# Extruder_Stepper_Motor_Driver.net
KiCad netlist of a schematic drawn in Altium Designer
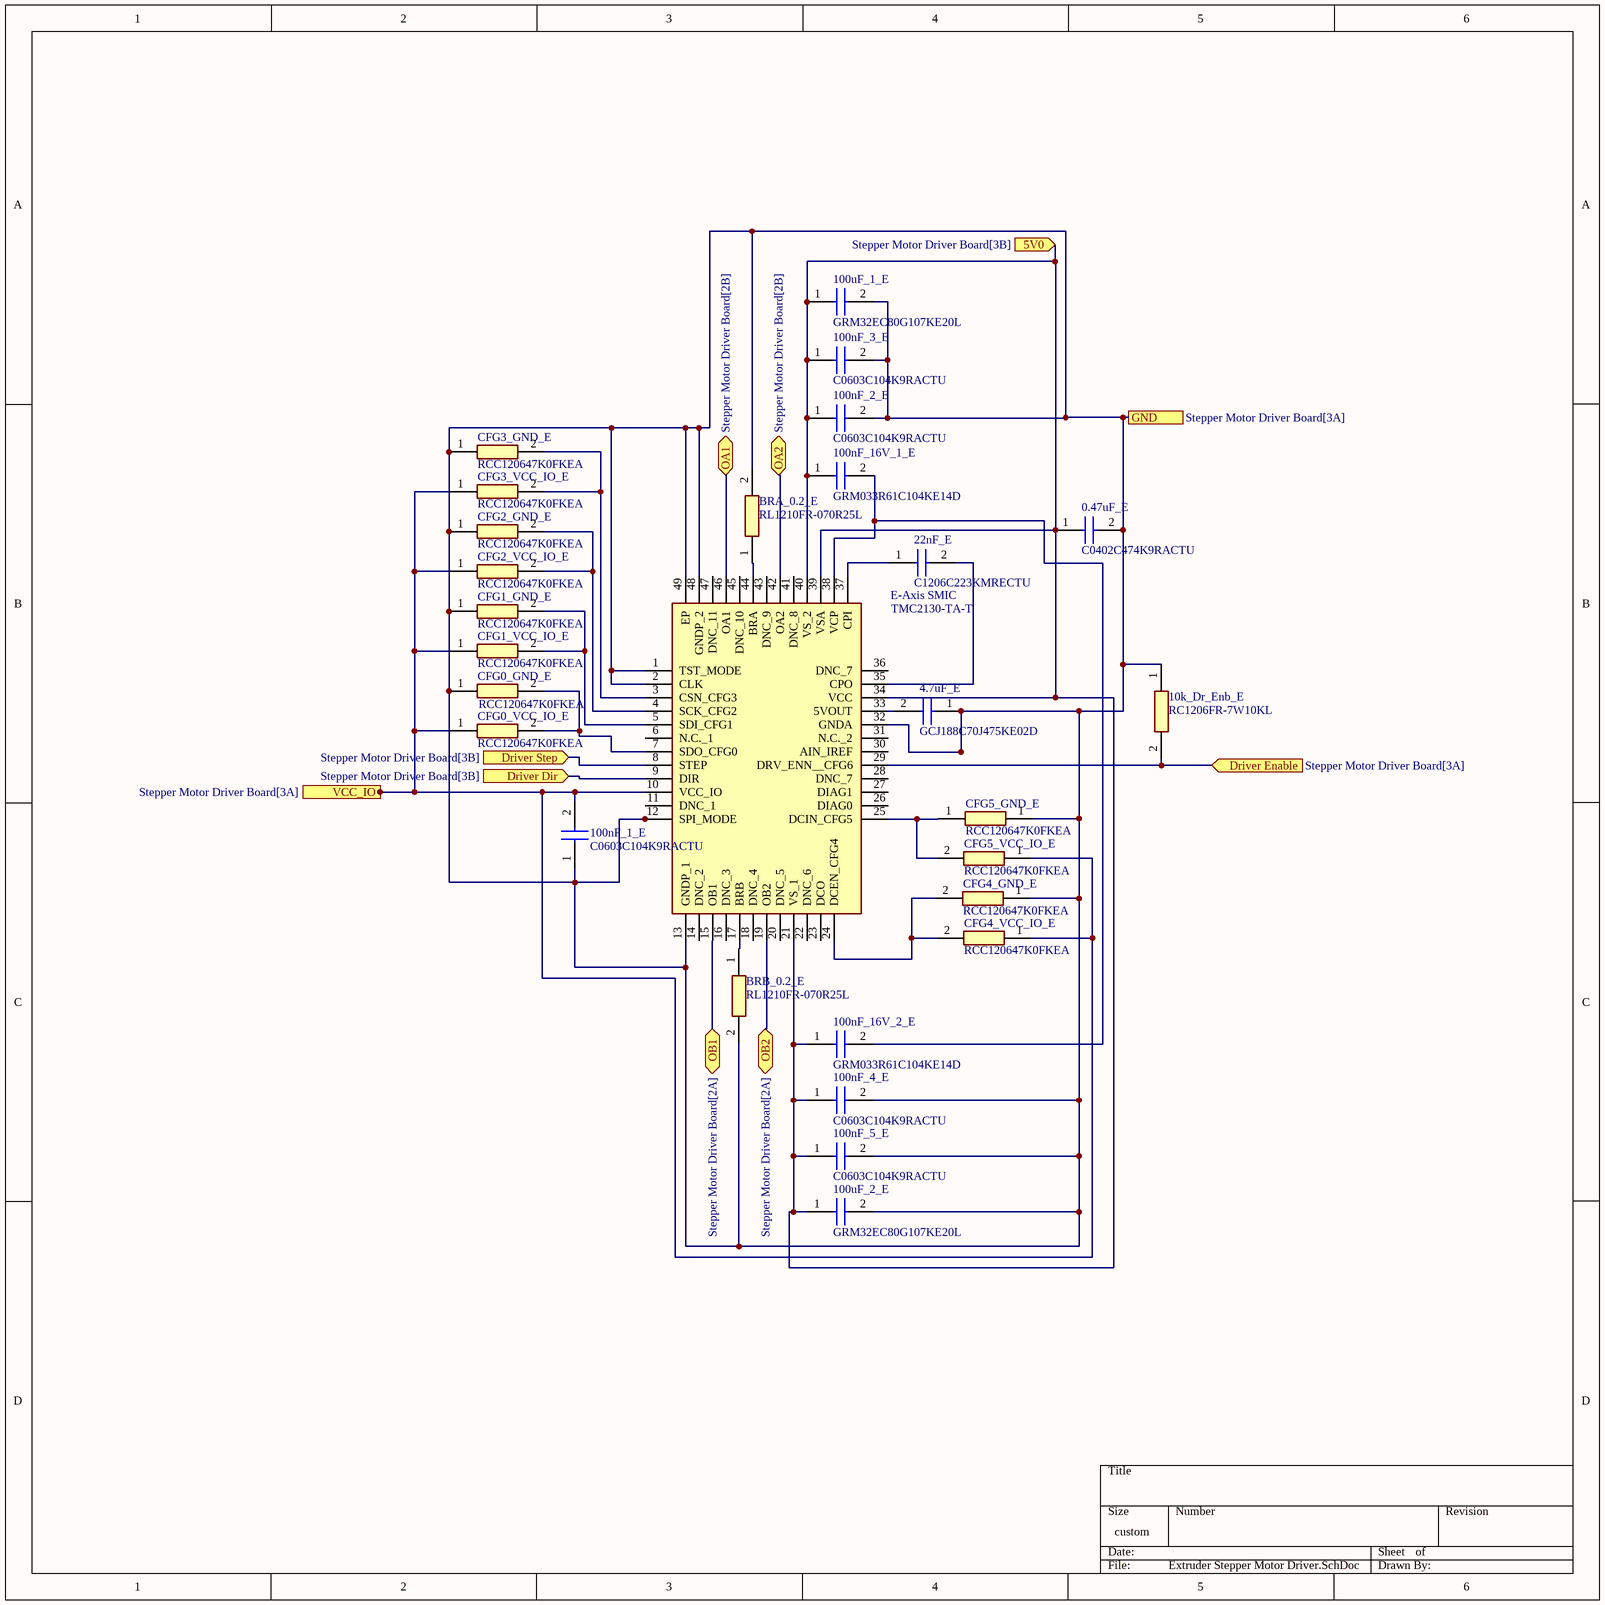
[diagram p0: Extruder Stepper Motor Driver.SchDoc]

(export (version "E")
  (design (tool "Eeschema 10.0.6"))
  (components
    (comp (ref "0.47uF_E")
      (value "C0402C474K9RACTU")
      (footprint "SamacSys:CAPC1005X55N")
      (description "Capacitor")
      (fields (field (name "MOUSER PART NUMBER") "80-C0402C474K9RACTU"))
      (libsource (lib "*") (part "C0402C474K9RACTU"))
    )
    (comp (ref "4.7uF_E")
      (value "GCJ188C70J475KE02D")
      (footprint "SamacSys:CAPC1608X100N")
      (description "Capacitor")
      (fields (field (name "MOUSER PART NUMBER") "81-GCJ188C70J475KE2D"))
      (libsource (lib "*") (part "GCJ188C70J475KE02D"))
    )
    (comp (ref "10k_Dr_Enb_E")
      (value "RC1206FR-7W10KL")
      (footprint "SamacSys:RESC3116X65N")
      (description "Resistor")
      (libsource (lib "*") (part "RC1206FR-7W10KL"))
    )
    (comp (ref "22nF_E")
      (value "C1206C223KMRECTU")
      (footprint "SamacSys:C1206")
      (description "Capacitor")
      (fields (field (name "MOUSER PART NUMBER") "80-C1206C223KMRECTU"))
      (libsource (lib "*") (part "C1206C223KMRECTU"))
    )
    (comp (ref "100nF_1_E")
      (value "C0603C104K9RACTU")
      (footprint "SamacSys:C0603")
      (description "Capacitor")
      (fields (field (name "MOUSER PART NUMBER") "80-C0603C104K9R"))
      (libsource (lib "*") (part "C0603C104K9RACTU"))
    )
    (comp (ref "100nF_2_E")
      (value "C0603C104K9RACTU")
      (footprint "SamacSys:C0603")
      (description "Capacitor")
      (fields (field (name "MOUSER PART NUMBER") "80-C0603C104K9R"))
      (libsource (lib "*") (part "C0603C104K9RACTU"))
    )
    (comp (ref "100nF_3_E")
      (value "C0603C104K9RACTU")
      (footprint "SamacSys:C0603")
      (description "Capacitor")
      (fields (field (name "MOUSER PART NUMBER") "80-C0603C104K9R"))
      (libsource (lib "*") (part "C0603C104K9RACTU"))
    )
    (comp (ref "100nF_4_E")
      (value "C0603C104K9RACTU")
      (footprint "SamacSys:C0603")
      (description "Capacitor")
      (fields (field (name "MOUSER PART NUMBER") "80-C0603C104K9R"))
      (libsource (lib "*") (part "C0603C104K9RACTU"))
    )
    (comp (ref "100nF_5_E")
      (value "C0603C104K9RACTU")
      (footprint "SamacSys:C0603")
      (description "Capacitor")
      (fields (field (name "MOUSER PART NUMBER") "80-C0603C104K9R"))
      (libsource (lib "*") (part "C0603C104K9RACTU"))
    )
    (comp (ref "100nF_16V_1_E")
      (value "GRM033R61C104KE14D")
      (footprint "SamacSys:CAPC0603X33N")
      (description "Capacitor")
      (fields (field (name "MOUSER PART NUMBER") "81-GRM033R61C104KE4D"))
      (libsource (lib "*") (part "GRM033R61C104KE14D"))
    )
    (comp (ref "100nF_16V_2_E")
      (value "GRM033R61C104KE14D")
      (footprint "SamacSys:CAPC0603X33N")
      (description "Capacitor")
      (fields (field (name "MOUSER PART NUMBER") "81-GRM033R61C104KE4D"))
      (libsource (lib "*") (part "GRM033R61C104KE14D"))
    )
    (comp (ref "100uF_1_E")
      (value "GRM32EC80G107KE20L")
      (footprint "SamacSys:CAPC3225X270N")
      (description "Capacitor")
      (fields (field (name "MOUSER PART NUMBER") "81-GRM32EC80G107KE0L"))
      (libsource (lib "*") (part "GRM32EC80G107KE20L"))
    )
    (comp (ref "100uF_2_E")
      (value "GRM32EC80G107KE20L")
      (footprint "SamacSys:CAPC3225X270N")
      (description "Capacitor")
      (fields (field (name "MOUSER PART NUMBER") "81-GRM32EC80G107KE0L"))
      (libsource (lib "*") (part "GRM32EC80G107KE20L"))
    )
    (comp (ref "BRA_0.2_E")
      (value "RL1210FR-070R25L")
      (footprint "SamacSys:RESC3126X65N")
      (description "Resistor")
      (fields (field (name "MOUSER PART NUMBER") "603-RL1210FR-070R25L"))
      (libsource (lib "") (part "RL1210FR-070R25L_1"))
    )
    (comp (ref "BRB_0.2_E")
      (value "RL1210FR-070R25L")
      (footprint "SamacSys:RESC3126X65N")
      (description "Resistor")
      (fields (field (name "MOUSER PART NUMBER") "603-RL1210FR-070R25L"))
      (libsource (lib "*") (part "RL1210FR-070R25L"))
    )
    (comp (ref "CFG0_GND_E")
      (value "RCC120647K0FKEA")
      (footprint "SamacSys:RCC1206_e3")
      (description "Resistor")
      (fields (field (name "MOUSER PART NUMBER") "71-RCC120647K0FKEA"))
      (libsource (lib "") (part "RCC120647K0FKEA_1"))
    )
    (comp (ref "CFG0_VCC_IO_E")
      (value "RCC120647K0FKEA")
      (footprint "SamacSys:RCC1206_e3")
      (description "Resistor")
      (fields (field (name "MOUSER PART NUMBER") "71-RCC120647K0FKEA"))
      (libsource (lib "") (part "RCC120647K0FKEA_1"))
    )
    (comp (ref "CFG1_GND_E")
      (value "RCC120647K0FKEA")
      (footprint "SamacSys:RCC1206_e3")
      (description "Resistor")
      (fields (field (name "MOUSER PART NUMBER") "71-RCC120647K0FKEA"))
      (libsource (lib "") (part "RCC120647K0FKEA_1"))
    )
    (comp (ref "CFG1_VCC_IO_E")
      (value "RCC120647K0FKEA")
      (footprint "SamacSys:RCC1206_e3")
      (description "Resistor")
      (fields (field (name "MOUSER PART NUMBER") "71-RCC120647K0FKEA"))
      (libsource (lib "") (part "RCC120647K0FKEA_1"))
    )
    (comp (ref "CFG2_GND_E")
      (value "RCC120647K0FKEA")
      (footprint "SamacSys:RCC1206_e3")
      (description "Resistor")
      (fields (field (name "MOUSER PART NUMBER") "71-RCC120647K0FKEA"))
      (libsource (lib "") (part "RCC120647K0FKEA_1"))
    )
    (comp (ref "CFG2_VCC_IO_E")
      (value "RCC120647K0FKEA")
      (footprint "SamacSys:RCC1206_e3")
      (description "Resistor")
      (fields (field (name "MOUSER PART NUMBER") "71-RCC120647K0FKEA"))
      (libsource (lib "") (part "RCC120647K0FKEA_1"))
    )
    (comp (ref "CFG3_GND_E")
      (value "RCC120647K0FKEA")
      (footprint "SamacSys:RCC1206_e3")
      (description "Resistor")
      (fields (field (name "MOUSER PART NUMBER") "71-RCC120647K0FKEA"))
      (libsource (lib "") (part "RCC120647K0FKEA_1"))
    )
    (comp (ref "CFG3_VCC_IO_E")
      (value "RCC120647K0FKEA")
      (footprint "SamacSys:RCC1206_e3")
      (description "Resistor")
      (fields (field (name "MOUSER PART NUMBER") "71-RCC120647K0FKEA"))
      (libsource (lib "") (part "RCC120647K0FKEA_1"))
    )
    (comp (ref "CFG4_GND_E")
      (value "RCC120647K0FKEA")
      (footprint "SamacSys:RCC1206_e3")
      (description "Resistor")
      (fields (field (name "MOUSER PART NUMBER") "71-RCC120647K0FKEA"))
      (libsource (lib "*") (part "RCC120647K0FKEA"))
    )
    (comp (ref "CFG4_VCC_IO_E")
      (value "RCC120647K0FKEA")
      (footprint "SamacSys:RCC1206_e3")
      (description "Resistor")
      (fields (field (name "MOUSER PART NUMBER") "71-RCC120647K0FKEA"))
      (libsource (lib "*") (part "RCC120647K0FKEA"))
    )
    (comp (ref "CFG5_GND_E")
      (value "RCC120647K0FKEA")
      (footprint "SamacSys:RCC1206_e3")
      (description "Resistor")
      (fields (field (name "MOUSER PART NUMBER") "71-RCC120647K0FKEA"))
      (libsource (lib "") (part "RCC120647K0FKEA_2"))
    )
    (comp (ref "CFG5_VCC_IO_E")
      (value "RCC120647K0FKEA")
      (footprint "SamacSys:RCC1206_e3")
      (description "Resistor")
      (fields (field (name "MOUSER PART NUMBER") "71-RCC120647K0FKEA"))
      (libsource (lib "*") (part "RCC120647K0FKEA"))
    )
    (comp (ref "E-Axis SMIC")
      (value "TMC2130-TA-T")
      (footprint "SamacSys:QFP50P900X900X120-49N")
      (description "Integrated Circuit")
      (fields (field (name "MOUSER PART NUMBER") "700-TMC2130-TA-T"))
      (libsource (lib "*") (part "TMC2130-TA-T"))
    )
  )
  (nets
    (net (code "1") (name "/5V0") (class "Default")
      (node (ref "0.47uF_E") (pin "1") (pinfunction "1_1") (pintype "passive"))
      (node (ref "100nF_16V_1_E") (pin "1") (pinfunction "1_1") (pintype "passive"))
      (node (ref "100nF_16V_2_E") (pin "1") (pinfunction "1_1") (pintype "passive"))
      (node (ref "100nF_2_E") (pin "1") (pinfunction "1_1") (pintype "passive"))
      (node (ref "100nF_3_E") (pin "1") (pinfunction "1_1") (pintype "passive"))
      (node (ref "100nF_4_E") (pin "1") (pinfunction "1_1") (pintype "passive"))
      (node (ref "100nF_5_E") (pin "1") (pinfunction "1_1") (pintype "passive"))
      (node (ref "100uF_1_E") (pin "1") (pinfunction "1_1") (pintype "passive"))
      (node (ref "100uF_2_E") (pin "1") (pinfunction "1_1") (pintype "passive"))
      (node (ref "E-Axis SMIC") (pin "21") (pinfunction "VS_1_21") (pintype "passive"))
      (node (ref "E-Axis SMIC") (pin "34") (pinfunction "VCC_34") (pintype "passive"))
      (node (ref "E-Axis SMIC") (pin "39") (pinfunction "VSA_39") (pintype "passive"))
      (node (ref "E-Axis SMIC") (pin "40") (pinfunction "VS_2_40") (pintype "passive"))
    )
    (net (code "2") (name "/Driver Dir") (class "Default")
      (node (ref "E-Axis SMIC") (pin "9") (pinfunction "DIR_9") (pintype "passive"))
    )
    (net (code "3") (name "/Driver Enable") (class "Default")
      (node (ref "10k_Dr_Enb_E") (pin "2") (pinfunction "2_2") (pintype "passive"))
      (node (ref "E-Axis SMIC") (pin "29") (pinfunction "DRV_ENN__CFG6_29") (pintype "passive"))
    )
    (net (code "4") (name "/Driver Step") (class "Default")
      (node (ref "E-Axis SMIC") (pin "8") (pinfunction "STEP_8") (pintype "passive"))
    )
    (net (code "5") (name "/GND") (class "Default")
      (node (ref "0.47uF_E") (pin "2") (pinfunction "2_2") (pintype "passive"))
      (node (ref "100nF_1_E") (pin "1") (pinfunction "1_1") (pintype "passive"))
      (node (ref "100nF_2_E") (pin "2") (pinfunction "2_2") (pintype "passive"))
      (node (ref "100nF_3_E") (pin "2") (pinfunction "2_2") (pintype "passive"))
      (node (ref "100nF_4_E") (pin "2") (pinfunction "2_2") (pintype "passive"))
      (node (ref "100nF_5_E") (pin "2") (pinfunction "2_2") (pintype "passive"))
      (node (ref "100uF_1_E") (pin "2") (pinfunction "2_2") (pintype "passive"))
      (node (ref "100uF_2_E") (pin "2") (pinfunction "2_2") (pintype "passive"))
      (node (ref "10k_Dr_Enb_E") (pin "1") (pinfunction "1_1") (pintype "passive"))
      (node (ref "4.7uF_E") (pin "1") (pinfunction "1_1") (pintype "passive"))
      (node (ref "BRA_0.2_E") (pin "2") (pinfunction "2_2") (pintype "passive"))
      (node (ref "BRB_0.2_E") (pin "2") (pinfunction "2_2") (pintype "passive"))
      (node (ref "CFG0_GND_E") (pin "1") (pinfunction "1_1") (pintype "passive"))
      (node (ref "CFG1_GND_E") (pin "1") (pinfunction "1_1") (pintype "passive"))
      (node (ref "CFG2_GND_E") (pin "1") (pinfunction "1_1") (pintype "passive"))
      (node (ref "CFG3_GND_E") (pin "1") (pinfunction "1_1") (pintype "passive"))
      (node (ref "CFG4_GND_E") (pin "1") (pinfunction "1_1") (pintype "passive"))
      (node (ref "CFG5_GND_E") (pin "1") (pinfunction "1_1") (pintype "passive"))
      (node (ref "E-Axis SMIC") (pin "1") (pinfunction "TST_MODE_1") (pintype "passive"))
      (node (ref "E-Axis SMIC") (pin "12") (pinfunction "SPI_MODE_12") (pintype "passive"))
      (node (ref "E-Axis SMIC") (pin "13") (pinfunction "GNDP_1_13") (pintype "passive"))
      (node (ref "E-Axis SMIC") (pin "2") (pinfunction "CLK_2") (pintype "passive"))
      (node (ref "E-Axis SMIC") (pin "32") (pinfunction "GNDA_32") (pintype "passive"))
      (node (ref "E-Axis SMIC") (pin "48") (pinfunction "GNDP_2_48") (pintype "passive"))
      (node (ref "E-Axis SMIC") (pin "49") (pinfunction "EP_49") (pintype "passive"))
    )
    (net (code "6") (name "/OA1") (class "Default")
      (node (ref "E-Axis SMIC") (pin "46") (pinfunction "OA1_46") (pintype "passive"))
    )
    (net (code "7") (name "/OA2") (class "Default")
      (node (ref "E-Axis SMIC") (pin "42") (pinfunction "OA2_42") (pintype "passive"))
    )
    (net (code "8") (name "/OB1") (class "Default")
      (node (ref "E-Axis SMIC") (pin "15") (pinfunction "OB1_15") (pintype "passive"))
    )
    (net (code "9") (name "/OB2") (class "Default")
      (node (ref "E-Axis SMIC") (pin "19") (pinfunction "OB2_19") (pintype "passive"))
    )
    (net (code "10") (name "/VCC_IO") (class "Default")
      (node (ref "100nF_1_E") (pin "2") (pinfunction "2_2") (pintype "passive"))
      (node (ref "CFG0_VCC_IO_E") (pin "1") (pinfunction "1_1") (pintype "passive"))
      (node (ref "CFG1_VCC_IO_E") (pin "1") (pinfunction "1_1") (pintype "passive"))
      (node (ref "CFG2_VCC_IO_E") (pin "1") (pinfunction "1_1") (pintype "passive"))
      (node (ref "CFG3_VCC_IO_E") (pin "1") (pinfunction "1_1") (pintype "passive"))
      (node (ref "CFG4_VCC_IO_E") (pin "1") (pinfunction "1_1") (pintype "passive"))
      (node (ref "CFG5_VCC_IO_E") (pin "1") (pinfunction "1_1") (pintype "passive"))
      (node (ref "E-Axis SMIC") (pin "10") (pinfunction "VCC_IO_10") (pintype "passive"))
    )
    (net (code "11") (name "Net-(E-Axis SMIC-5VOUT)") (class "Default")
      (node (ref "4.7uF_E") (pin "2") (pinfunction "2_2") (pintype "passive"))
      (node (ref "E-Axis SMIC") (pin "33") (pinfunction "5VOUT_33") (pintype "passive"))
    )
    (net (code "12") (name "Net-(E-Axis SMIC-BRA)") (class "Default")
      (node (ref "BRA_0.2_E") (pin "1") (pinfunction "1_1") (pintype "passive"))
      (node (ref "E-Axis SMIC") (pin "44") (pinfunction "BRA_44") (pintype "passive"))
    )
    (net (code "13") (name "Net-(E-Axis SMIC-BRB)") (class "Default")
      (node (ref "BRB_0.2_E") (pin "1") (pinfunction "1_1") (pintype "passive"))
      (node (ref "E-Axis SMIC") (pin "17") (pinfunction "BRB_17") (pintype "passive"))
    )
    (net (code "14") (name "Net-(E-Axis SMIC-CPI)") (class "Default")
      (node (ref "22nF_E") (pin "1") (pinfunction "1_1") (pintype "passive"))
      (node (ref "E-Axis SMIC") (pin "37") (pinfunction "CPI_37") (pintype "passive"))
    )
    (net (code "15") (name "Net-(E-Axis SMIC-CPO)") (class "Default")
      (node (ref "22nF_E") (pin "2") (pinfunction "2_2") (pintype "passive"))
      (node (ref "E-Axis SMIC") (pin "35") (pinfunction "CPO_35") (pintype "passive"))
    )
    (net (code "16") (name "Net-(E-Axis SMIC-CSN_CFG3)") (class "Default")
      (node (ref "CFG3_GND_E") (pin "2") (pinfunction "2_2") (pintype "passive"))
      (node (ref "CFG3_VCC_IO_E") (pin "2") (pinfunction "2_2") (pintype "passive"))
      (node (ref "E-Axis SMIC") (pin "3") (pinfunction "CSN_CFG3_3") (pintype "passive"))
    )
    (net (code "17") (name "Net-(E-Axis SMIC-DCEN_CFG4)") (class "Default")
      (node (ref "CFG4_GND_E") (pin "2") (pinfunction "2_2") (pintype "passive"))
      (node (ref "CFG4_VCC_IO_E") (pin "2") (pinfunction "2_2") (pintype "passive"))
      (node (ref "E-Axis SMIC") (pin "24") (pinfunction "DCEN_CFG4_24") (pintype "passive"))
    )
    (net (code "18") (name "Net-(E-Axis SMIC-DCIN_CFG5)") (class "Default")
      (node (ref "CFG5_GND_E") (pin "1") (pinfunction "1_1") (pintype "passive"))
      (node (ref "CFG5_VCC_IO_E") (pin "2") (pinfunction "2_2") (pintype "passive"))
      (node (ref "E-Axis SMIC") (pin "25") (pinfunction "DCIN_CFG5_25") (pintype "passive"))
    )
    (net (code "19") (name "Net-(E-Axis SMIC-SCK_CFG2)") (class "Default")
      (node (ref "CFG2_GND_E") (pin "2") (pinfunction "2_2") (pintype "passive"))
      (node (ref "CFG2_VCC_IO_E") (pin "2") (pinfunction "2_2") (pintype "passive"))
      (node (ref "E-Axis SMIC") (pin "4") (pinfunction "SCK_CFG2_4") (pintype "passive"))
    )
    (net (code "20") (name "Net-(E-Axis SMIC-SDI_CFG1)") (class "Default")
      (node (ref "CFG1_GND_E") (pin "2") (pinfunction "2_2") (pintype "passive"))
      (node (ref "CFG1_VCC_IO_E") (pin "2") (pinfunction "2_2") (pintype "passive"))
      (node (ref "E-Axis SMIC") (pin "5") (pinfunction "SDI_CFG1_5") (pintype "passive"))
    )
    (net (code "21") (name "Net-(E-Axis SMIC-SDO_CFG0)") (class "Default")
      (node (ref "CFG0_GND_E") (pin "2") (pinfunction "2_2") (pintype "passive"))
      (node (ref "CFG0_VCC_IO_E") (pin "2") (pinfunction "2_2") (pintype "passive"))
      (node (ref "E-Axis SMIC") (pin "7") (pinfunction "SDO_CFG0_7") (pintype "passive"))
    )
    (net (code "22") (name "Net-(E-Axis SMIC-VCP)") (class "Default")
      (node (ref "100nF_16V_1_E") (pin "2") (pinfunction "2_2") (pintype "passive"))
      (node (ref "100nF_16V_2_E") (pin "2") (pinfunction "2_2") (pintype "passive"))
      (node (ref "E-Axis SMIC") (pin "38") (pinfunction "VCP_38") (pintype "passive"))
    )
    (net (code "23") (name "unconnected-(E-Axis SMIC-AIN_IREF-Pad30)") (class "Default")
      (node (ref "E-Axis SMIC") (pin "30") (pinfunction "AIN_IREF_30") (pintype "passive"))
    )
    (net (code "24") (name "unconnected-(E-Axis SMIC-DCO-Pad23)") (class "Default")
      (node (ref "E-Axis SMIC") (pin "23") (pinfunction "DCO_23") (pintype "passive"))
    )
    (net (code "25") (name "unconnected-(E-Axis SMIC-DIAG0-Pad26)") (class "Default")
      (node (ref "E-Axis SMIC") (pin "26") (pinfunction "DIAG0_26") (pintype "passive"))
    )
    (net (code "26") (name "unconnected-(E-Axis SMIC-DIAG1-Pad27)") (class "Default")
      (node (ref "E-Axis SMIC") (pin "27") (pinfunction "DIAG1_27") (pintype "passive"))
    )
    (net (code "27") (name "unconnected-(E-Axis SMIC-DNC_1-Pad11)") (class "Default")
      (node (ref "E-Axis SMIC") (pin "11") (pinfunction "DNC_1_11") (pintype "passive"))
    )
    (net (code "28") (name "unconnected-(E-Axis SMIC-DNC_2-Pad14)") (class "Default")
      (node (ref "E-Axis SMIC") (pin "14") (pinfunction "DNC_2_14") (pintype "passive"))
    )
    (net (code "29") (name "unconnected-(E-Axis SMIC-DNC_3-Pad16)") (class "Default")
      (node (ref "E-Axis SMIC") (pin "16") (pinfunction "DNC_3_16") (pintype "passive"))
    )
    (net (code "30") (name "unconnected-(E-Axis SMIC-DNC_4-Pad18)") (class "Default")
      (node (ref "E-Axis SMIC") (pin "18") (pinfunction "DNC_4_18") (pintype "passive"))
    )
    (net (code "31") (name "unconnected-(E-Axis SMIC-DNC_5-Pad20)") (class "Default")
      (node (ref "E-Axis SMIC") (pin "20") (pinfunction "DNC_5_20") (pintype "passive"))
    )
    (net (code "32") (name "unconnected-(E-Axis SMIC-DNC_6-Pad22)") (class "Default")
      (node (ref "E-Axis SMIC") (pin "22") (pinfunction "DNC_6_22") (pintype "passive"))
    )
    (net (code "33") (name "unconnected-(E-Axis SMIC-DNC_7-Pad28)") (class "Default")
      (node (ref "E-Axis SMIC") (pin "28") (pinfunction "DNC_7_28") (pintype "passive"))
    )
    (net (code "34") (name "unconnected-(E-Axis SMIC-DNC_7-Pad36)") (class "Default")
      (node (ref "E-Axis SMIC") (pin "36") (pinfunction "DNC_7_36") (pintype "passive"))
    )
    (net (code "35") (name "unconnected-(E-Axis SMIC-DNC_8-Pad41)") (class "Default")
      (node (ref "E-Axis SMIC") (pin "41") (pinfunction "DNC_8_41") (pintype "passive"))
    )
    (net (code "36") (name "unconnected-(E-Axis SMIC-DNC_9-Pad43)") (class "Default")
      (node (ref "E-Axis SMIC") (pin "43") (pinfunction "DNC_9_43") (pintype "passive"))
    )
    (net (code "37") (name "unconnected-(E-Axis SMIC-DNC_10-Pad45)") (class "Default")
      (node (ref "E-Axis SMIC") (pin "45") (pinfunction "DNC_10_45") (pintype "passive"))
    )
    (net (code "38") (name "unconnected-(E-Axis SMIC-DNC_11-Pad47)") (class "Default")
      (node (ref "E-Axis SMIC") (pin "47") (pinfunction "DNC_11_47") (pintype "passive"))
    )
    (net (code "39") (name "unconnected-(E-Axis SMIC-N.C._1-Pad6)") (class "Default")
      (node (ref "E-Axis SMIC") (pin "6") (pinfunction "N.C._1_6") (pintype "passive"))
    )
    (net (code "40") (name "unconnected-(E-Axis SMIC-N.C._2-Pad31)") (class "Default")
      (node (ref "E-Axis SMIC") (pin "31") (pinfunction "N.C._2_31") (pintype "passive"))
    )
  )
)
